# rpi.net
KiCad netlist of a schematic drawn in Altium Designer
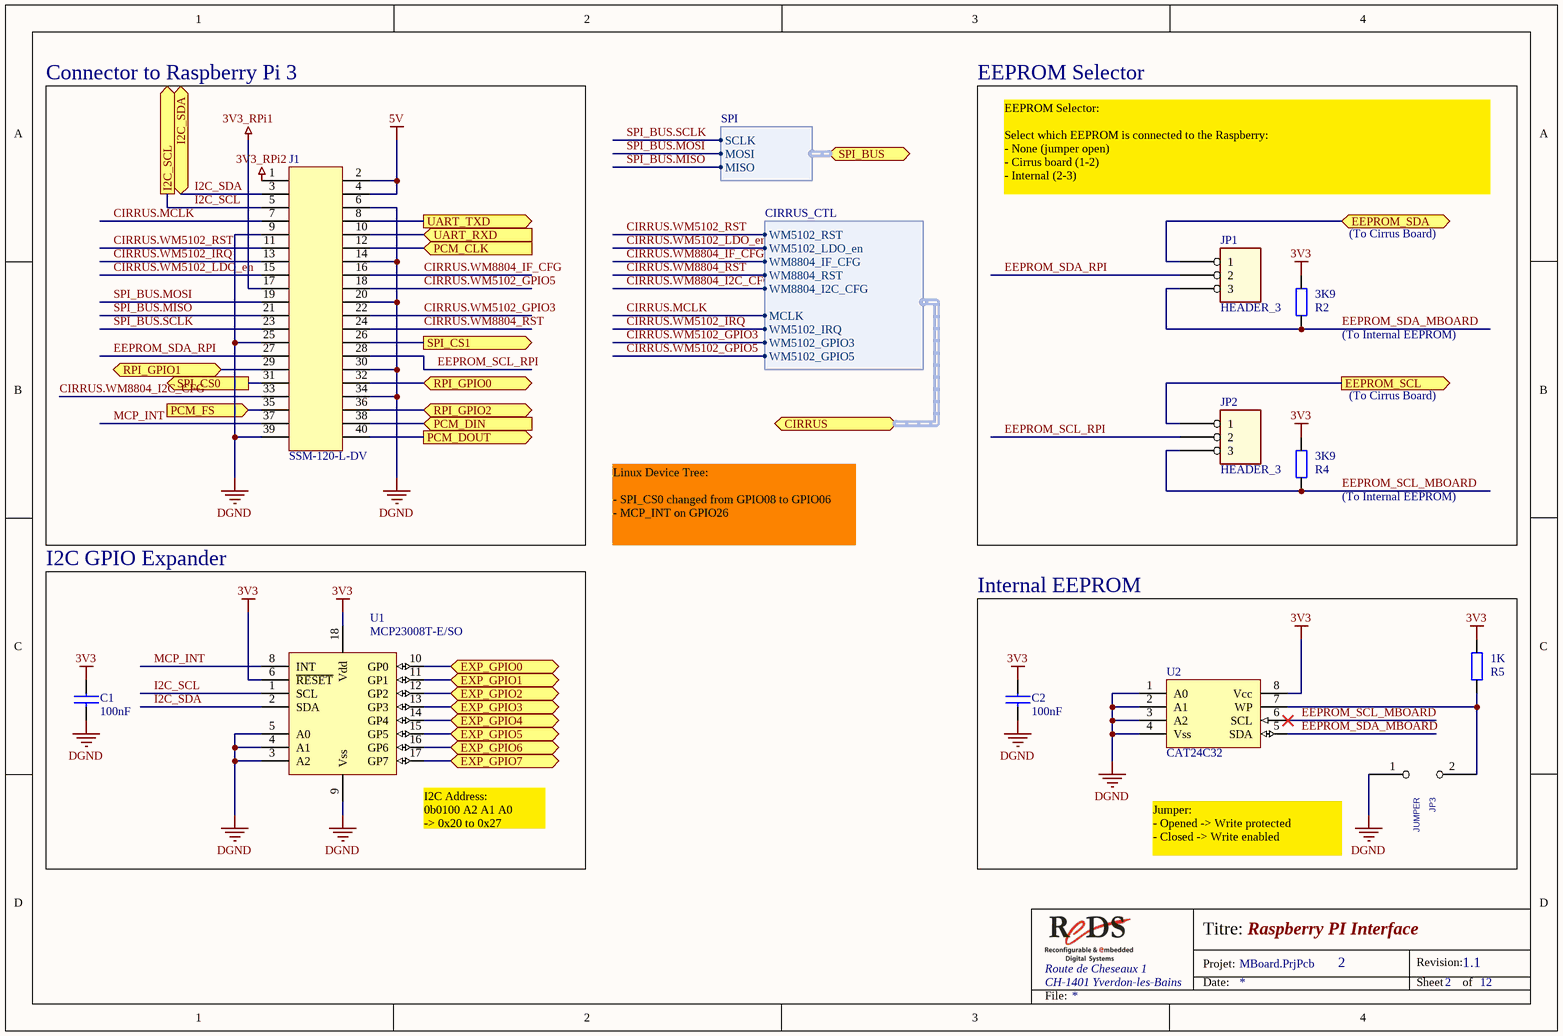
[diagram p0: rpi.SchDoc]

(export (version "E")
  (design (tool "Eeschema 10.0.6"))
  (components
    (comp (ref "C1")
      (value "100nF")
      (footprint "SM/C_0603")
      (description "Ceramic multi-layer")
      (fields (field (name "MANUFACTURER") "AVX") (field (name "VOLTAGE") "16V"))
      (libsource (lib "Database_heig-vd") (part "Cap"))
    )
    (comp (ref "C2")
      (value "100nF")
      (footprint "SM/C_0603")
      (description "Ceramic multi-layer")
      (fields (field (name "MANUFACTURER") "AVX") (field (name "VOLTAGE") "16V"))
      (libsource (lib "Database_heig-vd") (part "Cap"))
    )
    (comp (ref "J1")
      (value "SSM-120-L-DV")
      (footprint "SSM-120")
      (description "Mating (female) connector for the RPi 3")
      (libsource (lib "MBoard") (part "SSM-120-L-DV"))
    )
    (comp (ref "JP1")
      (value "HEADER_3")
      (footprint "BLKCON.100/VH/TM1SQ/W.100/3")
      (description "Barrette simple 3 poles 2.54mm")
      (fields (field (name "MANUFACTURER") "TE Connectivity"))
      (libsource (lib "Database_heig-vd") (part "HEADER_3"))
    )
    (comp (ref "JP2")
      (value "HEADER_3")
      (footprint "BLKCON.100/VH/TM1SQ/W.100/3")
      (description "Barrette simple 3 poles 2.54mm")
      (fields (field (name "MANUFACTURER") "TE Connectivity"))
      (libsource (lib "Database_heig-vd") (part "HEADER_3"))
    )
    (comp (ref "JP3")
      (value "JUMPER")
      (description "Barrette simple 2 poles 2.54mm")
      (fields (field (name "MANUFACTURER") "TE Connectivity"))
      (libsource (lib "Database_heig-vd") (part "JUMPER"))
    )
    (comp (ref "R2")
      (value "3K9")
      (footprint "SM/R_0603")
      (description "Résistance 0603 63mW 1% 3K9")
      (fields (field (name "MANUFACTURER") "Multicomp") (field (name "POWER") "63mW"))
      (libsource (lib "Database_heig-vd") (part "Res"))
    )
    (comp (ref "R4")
      (value "3K9")
      (footprint "SM/R_0603")
      (description "Résistance 0603 63mW 1% 3K9")
      (fields (field (name "MANUFACTURER") "Multicomp") (field (name "POWER") "63mW"))
      (libsource (lib "Database_heig-vd") (part "Res"))
    )
    (comp (ref "R5")
      (value "1K")
      (footprint "SM/R_0603")
      (description "Résistance 0603 63mW 1% 1K")
      (fields (field (name "MANUFACTURER") "Multicomp") (field (name "POWER") "63mW"))
      (libsource (lib "Database_heig-vd") (part "Res"))
    )
    (comp (ref "U1")
      (value "MCP23008T-E/SO")
      (footprint "SOIC-18 - W")
      (description "8-Bit I/O Expander with Serial Interface (SOIC)")
      (libsource (lib "MBoard") (part "MCP23008T-E/SO"))
    )
    (comp (ref "U2")
      (value "CAT24C32")
      (footprint "SOIC-8 - N")
      (description "32-Kb I2C CMOS Serial  EEPROM")
      (libsource (lib "MBoard") (part "CAT24C32W"))
    )
  )
  (nets
    (net (code "3") (name "/CIRRUS.MCLK") (class "Default")
      (node (ref "J1") (pin "7") (pinfunction "7_7") (pintype "passive"))
    )
    (net (code "4") (name "/CIRRUS.WM5102_GPIO3") (class "Default")
      (node (ref "J1") (pin "22") (pinfunction "22_22") (pintype "passive"))
    )
    (net (code "5") (name "/CIRRUS.WM5102_GPIO5") (class "Default")
      (node (ref "J1") (pin "18") (pinfunction "18_18") (pintype "passive"))
    )
    (net (code "6") (name "/CIRRUS.WM5102_IRQ") (class "Default")
      (node (ref "J1") (pin "13") (pinfunction "13_13") (pintype "passive"))
    )
    (net (code "7") (name "/CIRRUS.WM5102_LDO_en") (class "Default")
      (node (ref "J1") (pin "15") (pinfunction "15_15") (pintype "passive"))
    )
    (net (code "8") (name "/CIRRUS.WM5102_RST") (class "Default")
      (node (ref "J1") (pin "11") (pinfunction "11_11") (pintype "passive"))
    )
    (net (code "9") (name "/CIRRUS.WM8804_I2C_CFG") (class "Default")
      (node (ref "J1") (pin "33") (pinfunction "33_33") (pintype "passive"))
    )
    (net (code "10") (name "/CIRRUS.WM8804_IF_CFG") (class "Default")
      (node (ref "J1") (pin "16") (pinfunction "16_16") (pintype "passive"))
    )
    (net (code "11") (name "/CIRRUS.WM8804_RST") (class "Default")
      (node (ref "J1") (pin "24") (pinfunction "24_24") (pintype "passive"))
    )
    (net (code "12") (name "/EEPROM_SCL") (class "Default")
      (node (ref "JP2") (pin "1") (pinfunction "1_1") (pintype "passive"))
    )
    (net (code "13") (name "/EEPROM_SCL_MBOARD") (class "Default")
      (node (ref "JP2") (pin "3") (pinfunction "3_3") (pintype "passive"))
      (node (ref "R4") (pin "2") (pinfunction "2_2") (pintype "passive"))
      (node (ref "U2") (pin "6") (pinfunction "SCL_6") (pintype "input"))
    )
    (net (code "14") (name "/EEPROM_SCL_RPI") (class "Default")
      (node (ref "J1") (pin "28") (pinfunction "28_28") (pintype "passive"))
      (node (ref "JP2") (pin "2") (pinfunction "2_2") (pintype "passive"))
    )
    (net (code "15") (name "/EEPROM_SDA") (class "Default")
      (node (ref "JP1") (pin "1") (pinfunction "1_1") (pintype "passive"))
    )
    (net (code "16") (name "/EEPROM_SDA_MBOARD") (class "Default")
      (node (ref "JP1") (pin "3") (pinfunction "3_3") (pintype "passive"))
      (node (ref "R2") (pin "2") (pinfunction "2_2") (pintype "passive"))
      (node (ref "U2") (pin "5") (pinfunction "SDA_5") (pintype "bidirectional"))
    )
    (net (code "17") (name "/EEPROM_SDA_RPI") (class "Default")
      (node (ref "J1") (pin "27") (pinfunction "27_27") (pintype "passive"))
      (node (ref "JP1") (pin "2") (pinfunction "2_2") (pintype "passive"))
    )
    (net (code "18") (name "/EXP_GPIO0") (class "Default")
      (node (ref "U1") (pin "10") (pinfunction "GP0_10") (pintype "bidirectional"))
    )
    (net (code "19") (name "/EXP_GPIO1") (class "Default")
      (node (ref "U1") (pin "11") (pinfunction "GP1_11") (pintype "bidirectional"))
    )
    (net (code "20") (name "/EXP_GPIO2") (class "Default")
      (node (ref "U1") (pin "12") (pinfunction "GP2_12") (pintype "bidirectional"))
    )
    (net (code "21") (name "/EXP_GPIO3") (class "Default")
      (node (ref "U1") (pin "13") (pinfunction "GP3_13") (pintype "bidirectional"))
    )
    (net (code "22") (name "/EXP_GPIO4") (class "Default")
      (node (ref "U1") (pin "14") (pinfunction "GP4_14") (pintype "bidirectional"))
    )
    (net (code "23") (name "/EXP_GPIO5") (class "Default")
      (node (ref "U1") (pin "15") (pinfunction "GP5_15") (pintype "bidirectional"))
    )
    (net (code "24") (name "/EXP_GPIO6") (class "Default")
      (node (ref "U1") (pin "16") (pinfunction "GP6_16") (pintype "bidirectional"))
    )
    (net (code "25") (name "/EXP_GPIO7") (class "Default")
      (node (ref "U1") (pin "17") (pinfunction "GP7_17") (pintype "bidirectional"))
    )
    (net (code "26") (name "/I2C_SCL") (class "Default")
      (node (ref "J1") (pin "5") (pinfunction "5_5") (pintype "passive"))
      (node (ref "U1") (pin "1") (pinfunction "SCL_1") (pintype "passive"))
    )
    (net (code "27") (name "/I2C_SDA") (class "Default")
      (node (ref "J1") (pin "3") (pinfunction "3_3") (pintype "passive"))
      (node (ref "U1") (pin "2") (pinfunction "SDA_2") (pintype "passive"))
    )
    (net (code "28") (name "/MCP_INT") (class "Default")
      (node (ref "J1") (pin "37") (pinfunction "37_37") (pintype "passive"))
      (node (ref "U1") (pin "8") (pinfunction "INT_8") (pintype "passive"))
    )
    (net (code "29") (name "/PCM_CLK") (class "Default")
      (node (ref "J1") (pin "12") (pinfunction "12_12") (pintype "passive"))
    )
    (net (code "30") (name "/PCM_DIN") (class "Default")
      (node (ref "J1") (pin "38") (pinfunction "38_38") (pintype "passive"))
    )
    (net (code "31") (name "/PCM_DOUT") (class "Default")
      (node (ref "J1") (pin "40") (pinfunction "40_40") (pintype "passive"))
    )
    (net (code "32") (name "/PCM_FS") (class "Default")
      (node (ref "J1") (pin "35") (pinfunction "35_35") (pintype "passive"))
    )
    (net (code "33") (name "/RPI_GPIO0") (class "Default")
      (node (ref "J1") (pin "32") (pinfunction "32_32") (pintype "passive"))
    )
    (net (code "34") (name "/RPI_GPIO1") (class "Default")
      (node (ref "J1") (pin "29") (pinfunction "29_29") (pintype "passive"))
    )
    (net (code "35") (name "/RPI_GPIO2") (class "Default")
      (node (ref "J1") (pin "36") (pinfunction "36_36") (pintype "passive"))
    )
    (net (code "36") (name "/SPI_BUS.MISO") (class "Default")
      (node (ref "J1") (pin "21") (pinfunction "21_21") (pintype "passive"))
    )
    (net (code "37") (name "/SPI_BUS.MOSI") (class "Default")
      (node (ref "J1") (pin "19") (pinfunction "19_19") (pintype "passive"))
    )
    (net (code "38") (name "/SPI_BUS.SCLK") (class "Default")
      (node (ref "J1") (pin "23") (pinfunction "23_23") (pintype "passive"))
    )
    (net (code "39") (name "/SPI_CS0") (class "Default")
      (node (ref "J1") (pin "31") (pinfunction "31_31") (pintype "passive"))
    )
    (net (code "40") (name "/SPI_CS1") (class "Default")
      (node (ref "J1") (pin "26") (pinfunction "26_26") (pintype "passive"))
    )
    (net (code "41") (name "/UART_RXD") (class "Default")
      (node (ref "J1") (pin "10") (pinfunction "10_10") (pintype "passive"))
    )
    (net (code "42") (name "/UART_TXD") (class "Default")
      (node (ref "J1") (pin "8") (pinfunction "8_8") (pintype "passive"))
    )
    (net (code "45") (name "3V3") (class "Default")
      (node (ref "C1") (pin "1") (pinfunction "1_1") (pintype "passive"))
      (node (ref "C2") (pin "1") (pinfunction "1_1") (pintype "passive"))
      (node (ref "R2") (pin "1") (pinfunction "1_1") (pintype "passive"))
      (node (ref "R4") (pin "1") (pinfunction "1_1") (pintype "passive"))
      (node (ref "R5") (pin "1") (pinfunction "1_1") (pintype "passive"))
      (node (ref "U1") (pin "18") (pinfunction "Vdd_18") (pintype "power_in"))
      (node (ref "U1") (pin "6") (pinfunction "~{RESET}_6") (pintype "passive"))
      (node (ref "U2") (pin "8") (pinfunction "Vcc_8") (pintype "power_in"))
    )
    (net (code "46") (name "3V3_RPi1") (class "Default")
      (node (ref "J1") (pin "17") (pinfunction "17_17") (pintype "passive"))
    )
    (net (code "47") (name "3V3_RPi2") (class "Default")
      (node (ref "J1") (pin "1") (pinfunction "1_1") (pintype "passive"))
    )
    (net (code "48") (name "5V") (class "Default")
      (node (ref "J1") (pin "2") (pinfunction "2_2") (pintype "passive"))
      (node (ref "J1") (pin "4") (pinfunction "4_4") (pintype "passive"))
    )
    (net (code "49") (name "DGND") (class "Default")
      (node (ref "C1") (pin "2") (pinfunction "2_2") (pintype "passive"))
      (node (ref "C2") (pin "2") (pinfunction "2_2") (pintype "passive"))
      (node (ref "J1") (pin "14") (pinfunction "14_14") (pintype "passive"))
      (node (ref "J1") (pin "20") (pinfunction "20_20") (pintype "passive"))
      (node (ref "J1") (pin "25") (pinfunction "25_25") (pintype "passive"))
      (node (ref "J1") (pin "30") (pinfunction "30_30") (pintype "passive"))
      (node (ref "J1") (pin "34") (pinfunction "34_34") (pintype "passive"))
      (node (ref "J1") (pin "39") (pinfunction "39_39") (pintype "passive"))
      (node (ref "J1") (pin "6") (pinfunction "6_6") (pintype "passive"))
      (node (ref "J1") (pin "9") (pinfunction "9_9") (pintype "passive"))
      (node (ref "JP3") (pin "1") (pinfunction "1_1") (pintype "passive"))
      (node (ref "U1") (pin "3") (pinfunction "A2_3") (pintype "passive"))
      (node (ref "U1") (pin "4") (pinfunction "A1_4") (pintype "passive"))
      (node (ref "U1") (pin "5") (pinfunction "A0_5") (pintype "passive"))
      (node (ref "U1") (pin "9") (pinfunction "Vss_9") (pintype "power_in"))
      (node (ref "U2") (pin "1") (pinfunction "A0_1") (pintype "passive"))
      (node (ref "U2") (pin "2") (pinfunction "A1_2") (pintype "passive"))
      (node (ref "U2") (pin "3") (pinfunction "A2_3") (pintype "passive"))
      (node (ref "U2") (pin "4") (pinfunction "Vss_4") (pintype "power_in"))
    )
    (net (code "50") (name "Net-(U2-WP)") (class "Default")
      (node (ref "JP3") (pin "2") (pinfunction "2_2") (pintype "passive"))
      (node (ref "R5") (pin "2") (pinfunction "2_2") (pintype "passive"))
      (node (ref "U2") (pin "7") (pinfunction "WP_7") (pintype "passive"))
    )
  )
)
